# remove_file.net
KiCad netlist of a schematic drawn in Altium Designer
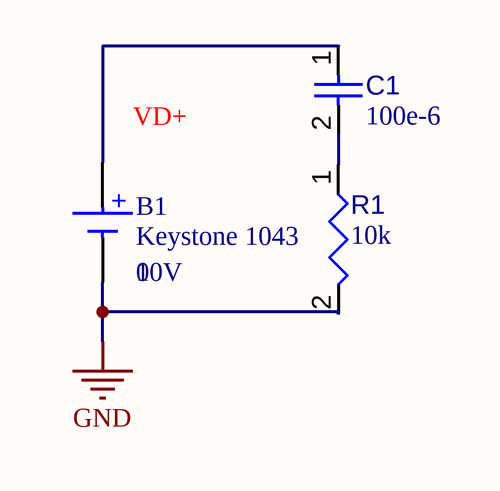
[diagram p0: remove_file.SchDoc]

(export (version "E")
  (design (tool "Eeschema 10.0.6"))
  (components
    (comp (ref "B1")
      (value "Keystone 1043")
      (fields (field (name "ALTIUM_VALUE") "10V") (field (name "OFFSET") "0"))
      (libsource (lib "SCH - BATTERY - KEYSTONE 1043") (part "Keystone 1043"))
    )
    (comp (ref "C1")
      (value "100e-6")
      (footprint "CAPC3216X180X20ML20")
      (description "Chip Capacitor, 1 uF, +/- 10%, 25 V, 1206 (3216 Metric)")
      (fields (field (name "TOLERANCE") "10%") (field (name "Comment") "Capacitor 1 uF +/- 10% 25 V 1206"))
      (libsource (lib "Jesus Fausto") (part "CAP-NP-2"))
    )
    (comp (ref "R1")
      (value "10k")
      (footprint "RESC1005X40X25ML05T05")
      (description "Chip Resistor, 10 KOhm, +/- 1%, 0.1 W, -55 to 155 degC, 0402 (1005 Metric)")
      (fields (field (name "POWER") "100mW") (field (name "TOLERANCE") "1%"))
      (libsource (lib "Jesus Fausto") (part "RES-2"))
    )
  )
  (nets
    (net (code "1") (name "GND") (class "Default")
      (node (ref "B1") (pin "2") (pinfunction "-_2") (pintype "passive"))
      (node (ref "R1") (pin "2") (pinfunction "2_2") (pintype "passive"))
    )
    (net (code "2") (name "Net-(B1-+)") (class "Default")
      (node (ref "B1") (pin "1") (pinfunction "+_1") (pintype "power_in"))
      (node (ref "C1") (pin "1") (pinfunction "1_1") (pintype "passive"))
    )
    (net (code "3") (name "Net-(C1-Pad2)") (class "Default")
      (node (ref "C1") (pin "2") (pinfunction "2_2") (pintype "passive"))
      (node (ref "R1") (pin "1") (pinfunction "1_1") (pintype "passive"))
    )
  )
)
